# SCH_PCB-Project_2025-10-18_1.net
KiCad netlist of a schematic drawn in EasyEDA
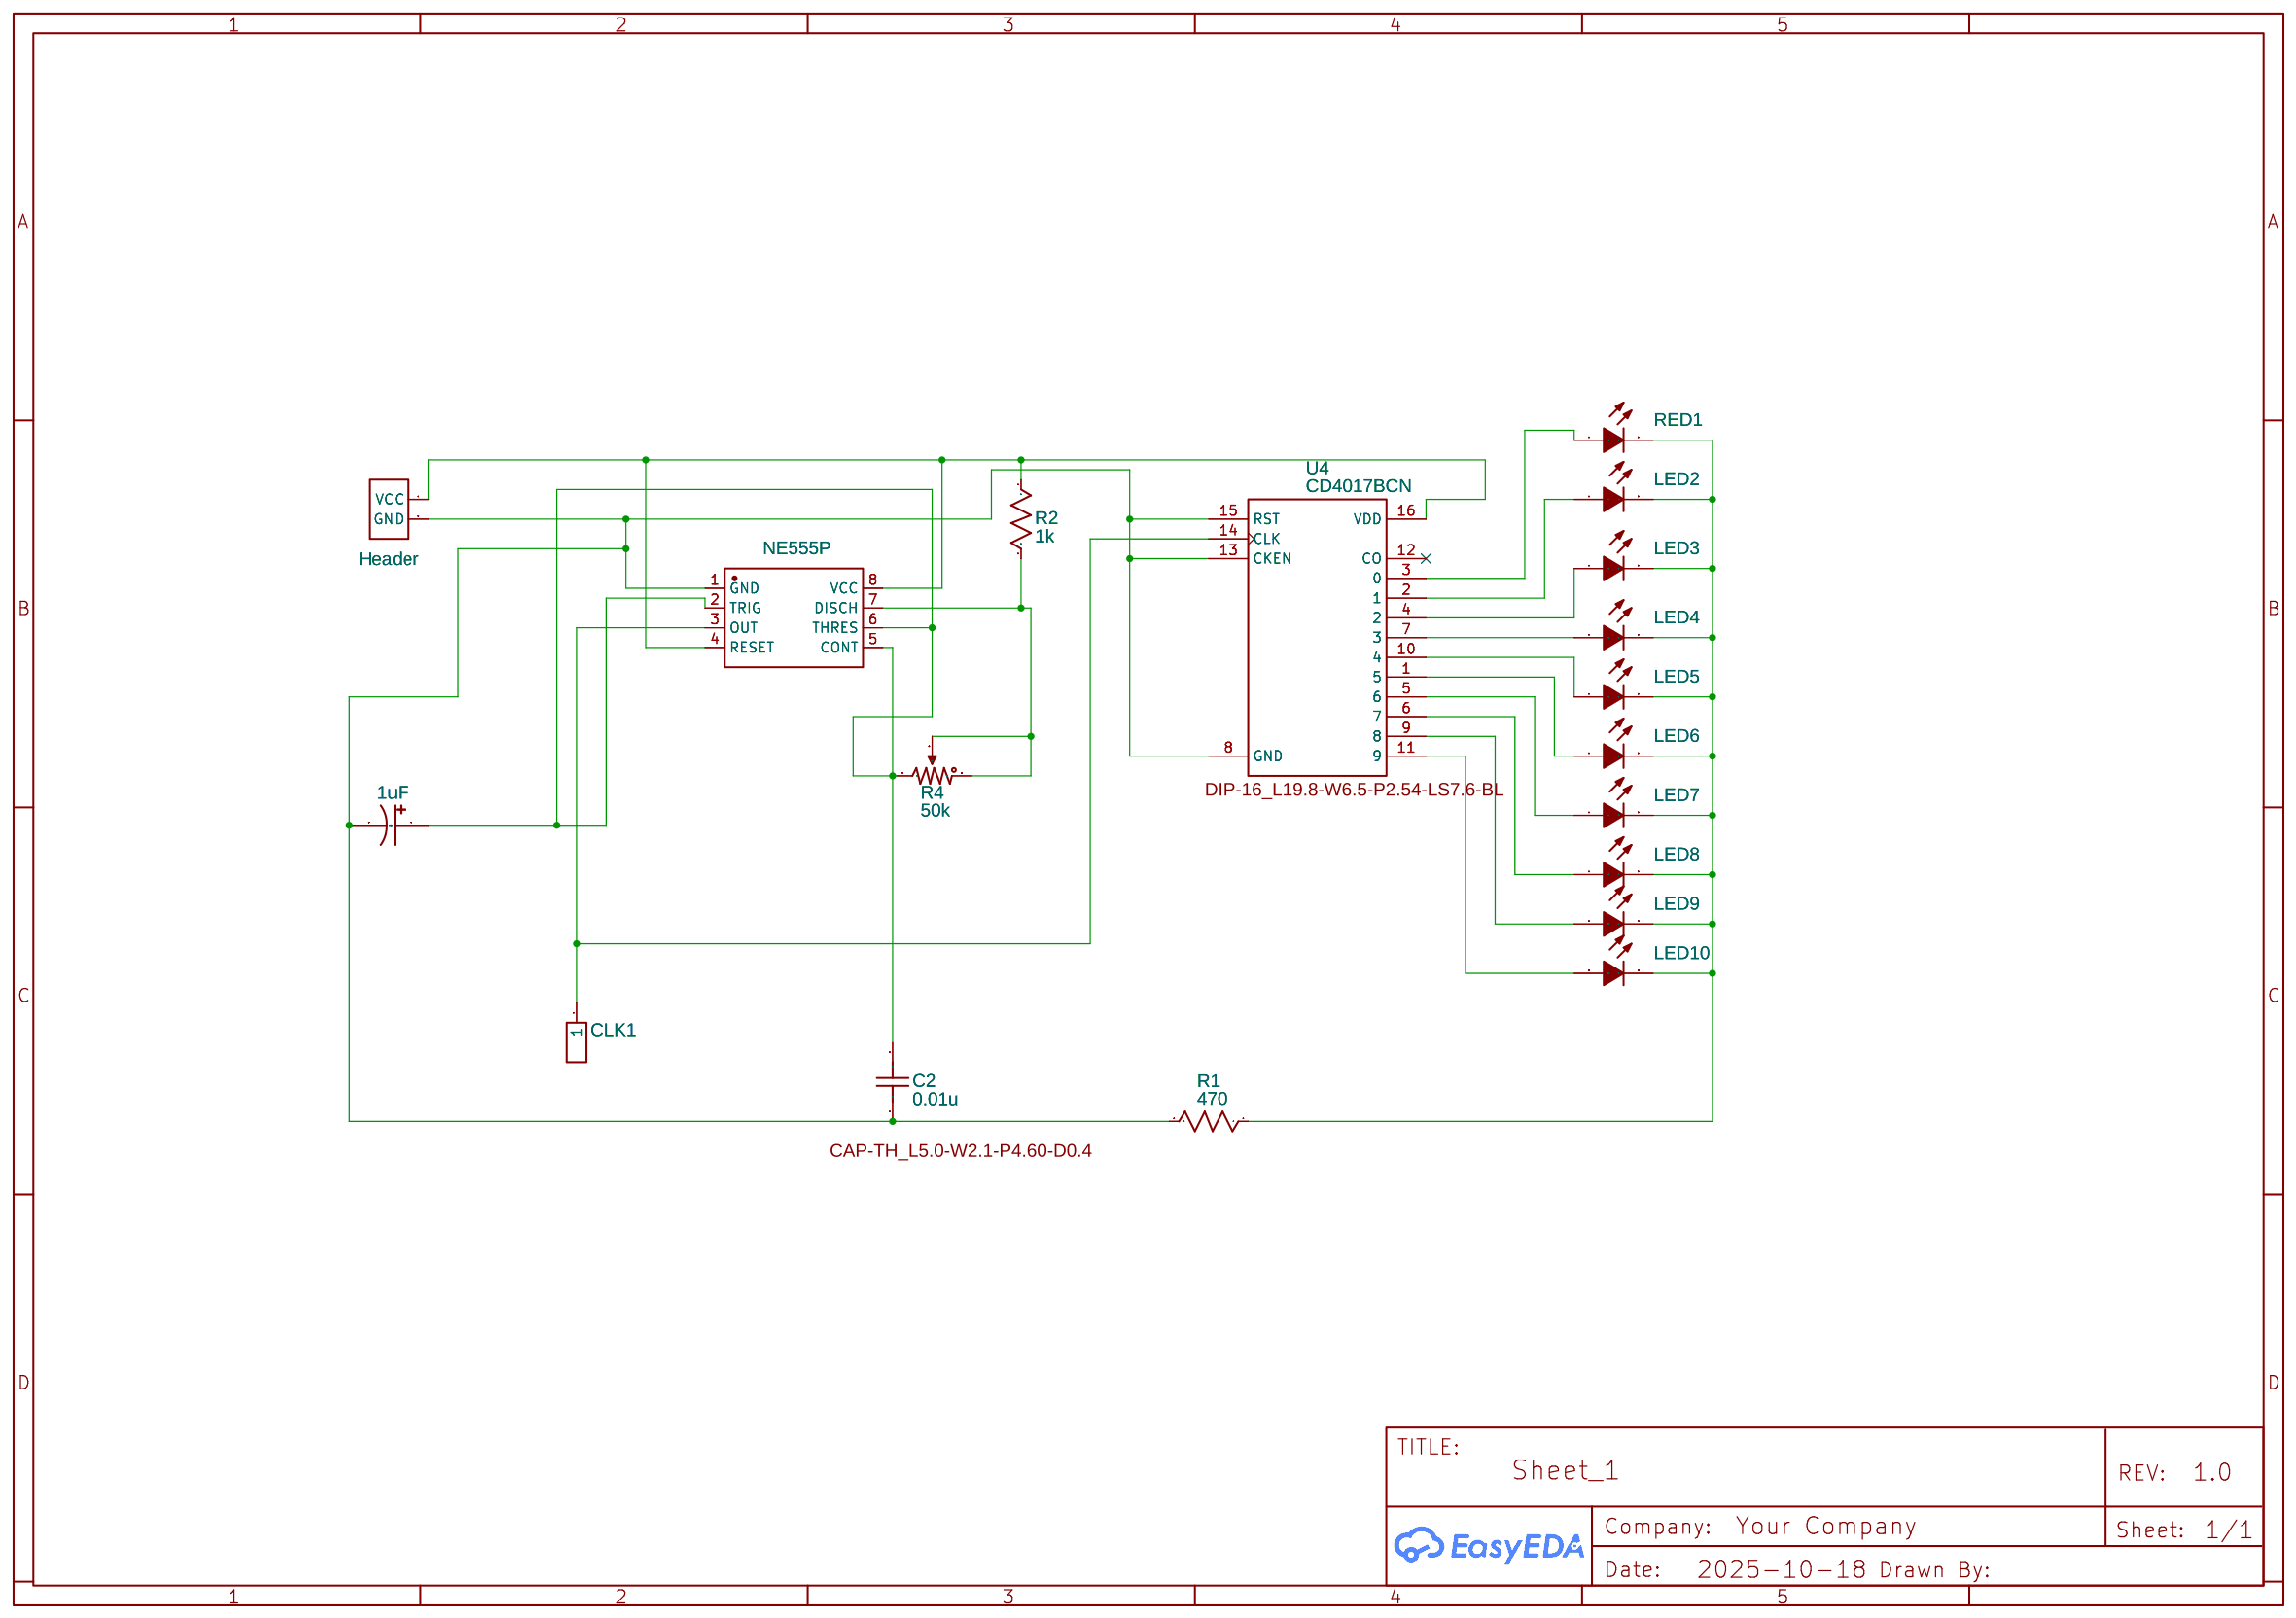
[diagram p0: schematic sheet]

(export (version "E")
  (design (tool "Eeschema 10.0.6"))
  (components
    (comp (ref "C1")
      (value "1uF")
      (fields (field (name "Manufacturer Part") "UVZ1H010MDD") (field (name "Manufacturer") "Nichicon(尼吉康)"))
      (libsource (lib "") (part "UVZ1H010MDD"))
    )
    (comp (ref "C2") (value "0.01u") (libsource (lib "") (part "C_0603_US")))
    (comp (ref "CLK1")
      (value "C81276")
      (fields
        (field (name "Manufacturer Part") "2.54-1*1P针")
        (field (name "Manufacturer") "BOOMELE(Boom Precision Elec)")
      )
      (libsource (lib "") (part "Header-Male-2.54_1x1"))
    )
    (comp (ref "H1") (value "Header") (libsource (lib "") (part "HEADER-FEMALE-2.54_1X2")))
    (comp (ref "LED2") (value "LED_5MM") (libsource (lib "") (part "LED_5MM")))
    (comp (ref "LED3") (value "LED_5MM") (libsource (lib "") (part "LED_5MM")))
    (comp (ref "LED4") (value "LED_5MM") (libsource (lib "") (part "LED_5MM")))
    (comp (ref "LED5") (value "LED_5MM") (libsource (lib "") (part "LED_5MM")))
    (comp (ref "LED6") (value "LED_5MM") (libsource (lib "") (part "LED_5MM")))
    (comp (ref "LED7") (value "LED_5MM") (libsource (lib "") (part "LED_5MM")))
    (comp (ref "LED8") (value "LED_5MM") (libsource (lib "") (part "LED_5MM")))
    (comp (ref "LED9") (value "LED_5MM") (libsource (lib "") (part "LED_5MM")))
    (comp (ref "LED10") (value "LED_5MM") (libsource (lib "") (part "LED_5MM")))
    (comp (ref "R1")
      (value "470")
      (fields (field (name "Manufacturer Part") "?"))
      (libsource (lib "") (part "Resistor_1"))
    )
    (comp (ref "R2")
      (value "1k")
      (fields (field (name "Manufacturer Part") "?"))
      (libsource (lib "") (part "Resistor"))
    )
    (comp (ref "R4")
      (value "50k")
      (fields (field (name "Manufacturer Part") "?"))
      (libsource (lib "") (part "Potentiometer"))
    )
    (comp (ref "RED1") (value "LED_5MM") (libsource (lib "") (part "LED_5MM_1")))
    (comp (ref "U2")
      (value "NE555P")
      (fields (field (name "Manufacturer") "TI(德州仪器)"))
      (libsource (lib "") (part "NE555P"))
    )
    (comp (ref "U4") (value "CD4017BCN") (libsource (lib "") (part "CD4017BCN")))
  )
  (nets
    (net (code "1") (name "Net-(H1-GND)") (class "Default")
      (node (ref "C1") (pin "2") (pinfunction "2_2") (pintype "unspecified"))
      (node (ref "C2") (pin "1") (pinfunction "1_1") (pintype "unspecified"))
      (node (ref "H1") (pin "2") (pinfunction "GND_2") (pintype "unspecified"))
      (node (ref "R1") (pin "2") (pinfunction "2_2") (pintype "unspecified"))
      (node (ref "U2") (pin "1") (pinfunction "GND_1") (pintype "unspecified"))
      (node (ref "U4") (pin "13") (pinfunction "CKEN_13") (pintype "unspecified"))
      (node (ref "U4") (pin "15") (pinfunction "RST_15") (pintype "unspecified"))
      (node (ref "U4") (pin "8") (pinfunction "GND_8") (pintype "passive"))
    )
    (net (code "2") (name "Net-(H1-VCC)") (class "Default")
      (node (ref "H1") (pin "1") (pinfunction "VCC_1") (pintype "unspecified"))
      (node (ref "R2") (pin "1") (pinfunction "1_1") (pintype "unspecified"))
      (node (ref "U2") (pin "4") (pinfunction "RESET_4") (pintype "unspecified"))
      (node (ref "U2") (pin "8") (pinfunction "VCC_8") (pintype "unspecified"))
      (node (ref "U4") (pin "16") (pinfunction "VDD_16") (pintype "passive"))
    )
    (net (code "3") (name "Net-(LED2-A)") (class "Default")
      (node (ref "LED2") (pin "1") (pinfunction "A_1") (pintype "input"))
      (node (ref "U4") (pin "2") (pinfunction "1_2") (pintype "output"))
    )
    (net (code "4") (name "Net-(LED3-A)") (class "Default")
      (node (ref "LED3") (pin "1") (pinfunction "A_1") (pintype "input"))
      (node (ref "U4") (pin "4") (pinfunction "2_4") (pintype "output"))
    )
    (net (code "5") (name "Net-(LED4-A)") (class "Default")
      (node (ref "LED4") (pin "1") (pinfunction "A_1") (pintype "input"))
      (node (ref "U4") (pin "7") (pinfunction "3_7") (pintype "output"))
    )
    (net (code "6") (name "Net-(LED5-A)") (class "Default")
      (node (ref "LED5") (pin "1") (pinfunction "A_1") (pintype "input"))
      (node (ref "U4") (pin "10") (pinfunction "4_10") (pintype "output"))
    )
    (net (code "7") (name "Net-(LED6-A)") (class "Default")
      (node (ref "LED6") (pin "1") (pinfunction "A_1") (pintype "input"))
      (node (ref "U4") (pin "1") (pinfunction "5_1") (pintype "output"))
    )
    (net (code "8") (name "Net-(LED7-A)") (class "Default")
      (node (ref "LED7") (pin "1") (pinfunction "A_1") (pintype "input"))
      (node (ref "U4") (pin "5") (pinfunction "6_5") (pintype "output"))
    )
    (net (code "9") (name "Net-(LED8-A)") (class "Default")
      (node (ref "LED8") (pin "1") (pinfunction "A_1") (pintype "input"))
      (node (ref "U4") (pin "6") (pinfunction "7_6") (pintype "output"))
    )
    (net (code "10") (name "Net-(LED9-A)") (class "Default")
      (node (ref "LED9") (pin "1") (pinfunction "A_1") (pintype "input"))
      (node (ref "U4") (pin "9") (pinfunction "8_9") (pintype "output"))
    )
    (net (code "11") (name "Net-(LED10-A)") (class "Default")
      (node (ref "LED10") (pin "1") (pinfunction "A_1") (pintype "input"))
      (node (ref "U4") (pin "11") (pinfunction "9_11") (pintype "output"))
    )
    (net (code "12") (name "Net-(LED10-K)") (class "Default")
      (node (ref "LED10") (pin "2") (pinfunction "K_2") (pintype "input"))
      (node (ref "LED2") (pin "2") (pinfunction "K_2") (pintype "input"))
      (node (ref "LED3") (pin "2") (pinfunction "K_2") (pintype "input"))
      (node (ref "LED4") (pin "2") (pinfunction "K_2") (pintype "input"))
      (node (ref "LED5") (pin "2") (pinfunction "K_2") (pintype "input"))
      (node (ref "LED6") (pin "2") (pinfunction "K_2") (pintype "input"))
      (node (ref "LED7") (pin "2") (pinfunction "K_2") (pintype "input"))
      (node (ref "LED8") (pin "2") (pinfunction "K_2") (pintype "input"))
      (node (ref "LED9") (pin "2") (pinfunction "K_2") (pintype "input"))
      (node (ref "R1") (pin "1") (pinfunction "1_1") (pintype "unspecified"))
      (node (ref "RED1") (pin "2") (pinfunction "K_2") (pintype "input"))
    )
    (net (code "13") (name "Net-(R4-2)") (class "Default")
      (node (ref "R2") (pin "2") (pinfunction "2_2") (pintype "unspecified"))
      (node (ref "R4") (pin "2") (pinfunction "3_2") (pintype "unspecified"))
      (node (ref "R4") (pin "3") (pinfunction "2_3") (pintype "unspecified"))
      (node (ref "U2") (pin "7") (pinfunction "DISCH_7") (pintype "unspecified"))
    )
    (net (code "14") (name "Net-(RED1-A)") (class "Default")
      (node (ref "RED1") (pin "1") (pinfunction "A_1") (pintype "input"))
      (node (ref "U4") (pin "3") (pinfunction "0_3") (pintype "output"))
    )
    (net (code "15") (name "Net-(U2-CONT)") (class "Default")
      (node (ref "C1") (pin "1") (pinfunction "1_1") (pintype "unspecified"))
      (node (ref "C2") (pin "2") (pinfunction "2_2") (pintype "unspecified"))
      (node (ref "R4") (pin "1") (pinfunction "1_1") (pintype "unspecified"))
      (node (ref "U2") (pin "2") (pinfunction "TRIG_2") (pintype "unspecified"))
      (node (ref "U2") (pin "5") (pinfunction "CONT_5") (pintype "unspecified"))
      (node (ref "U2") (pin "6") (pinfunction "THRES_6") (pintype "unspecified"))
    )
    (net (code "16") (name "Net-(U2-OUT)") (class "Default")
      (node (ref "CLK1") (pin "1") (pinfunction "1_1") (pintype "unspecified"))
      (node (ref "U2") (pin "3") (pinfunction "OUT_3") (pintype "unspecified"))
      (node (ref "U4") (pin "14") (pinfunction "CLK_14") (pintype "unspecified"))
    )
    (net (code "17") (name "unconnected-(U4-CO-Pad12)") (class "Default")
      (node (ref "U4") (pin "12") (pinfunction "CO_12") (pintype "output+no_connect"))
    )
  )
)
